# 12_SPI_FLASH.net
KiCad netlist of a schematic drawn in Altium Designer
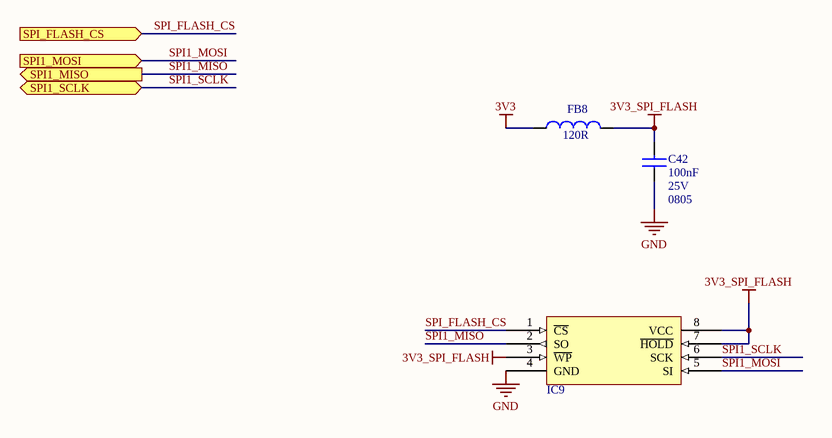
[diagram p0: 12.SPI_FLASH.SchDoc]

(export (version "E")
  (design (tool "Eeschema 10.0.6"))
  (components
    (comp (ref "C42")
      (value "CAP_NP")
      (footprint "CAPC2012X100N_EIA0805")
      (description "CAP CER 0.1UF 25V X7R 0805")
      (fields
        (field (name "PART NUMBER") "SCAP00300093")
        (field (name "CAPACITANCE") "100nF")
        (field (name "TOLERANCE") "±10%")
        (field (name "VOLTAGE - RATED") "25V")
        (field (name "PACKAGE / CASE") "0805")
      )
      (libsource (lib "ComponentDatabase") (part "CAP_NP"))
    )
    (comp (ref "FB8")
      (value "BEAD")
      (footprint "FILC2012X100N_EIA0805")
      (description "FERRITE CHIP POWER 120 OHM SMD")
      (fields
        (field (name "PART NUMBER") "SFIL00005")
        (field (name "IMPEDANCE") "120R")
        (field (name "MANUFACTURER") "Laird-Signal Integrity Products")
      )
      (libsource (lib "ComponentDatabase") (part "BEAD"))
    )
    (comp (ref "IC9")
      (value "W25Q16")
      (footprint "SOIC127P780X216-8N")
      (description "IC FLASH 16MBIT 104MHZ 8SOIC")
      (fields (field (name "PART NUMBER") "SMEM00015") (field (name "VOLTAGE") "2.7 V ~ 3.6 V"))
      (libsource (lib "ComponentDatabase") (part "W25Q16"))
    )
  )
  (nets
    (net (code "1") (name "/SPI1_MISO") (class "Default")
      (node (ref "IC9") (pin "2") (pinfunction "SO_2") (pintype "output"))
    )
    (net (code "2") (name "/SPI1_MOSI") (class "Default")
      (node (ref "IC9") (pin "5") (pinfunction "SI_5") (pintype "input"))
    )
    (net (code "3") (name "/SPI1_SCLK") (class "Default")
      (node (ref "IC9") (pin "6") (pinfunction "SCK_6") (pintype "input"))
    )
    (net (code "4") (name "/SPI_FLASH_CS") (class "Default")
      (node (ref "IC9") (pin "1") (pinfunction "~{CS}_1") (pintype "input"))
    )
    (net (code "5") (name "3V3") (class "Default")
      (node (ref "FB8") (pin "1") (pinfunction "1_1") (pintype "passive"))
    )
    (net (code "6") (name "3V3_SPI_FLASH") (class "Default")
      (node (ref "C42") (pin "2") (pinfunction "2_2") (pintype "passive"))
      (node (ref "FB8") (pin "2") (pinfunction "2_2") (pintype "passive"))
      (node (ref "IC9") (pin "3") (pinfunction "~{WP}_3") (pintype "input"))
      (node (ref "IC9") (pin "7") (pinfunction "~{HOLD}_7") (pintype "input"))
      (node (ref "IC9") (pin "8") (pinfunction "VCC_8") (pintype "power_in"))
    )
    (net (code "7") (name "GND") (class "Default")
      (node (ref "C42") (pin "1") (pinfunction "1_1") (pintype "passive"))
      (node (ref "IC9") (pin "4") (pinfunction "GND_4") (pintype "power_in"))
    )
  )
)
